# Rover_BeagleBone_Cape.net
KiCad netlist of a schematic drawn in EAGLE
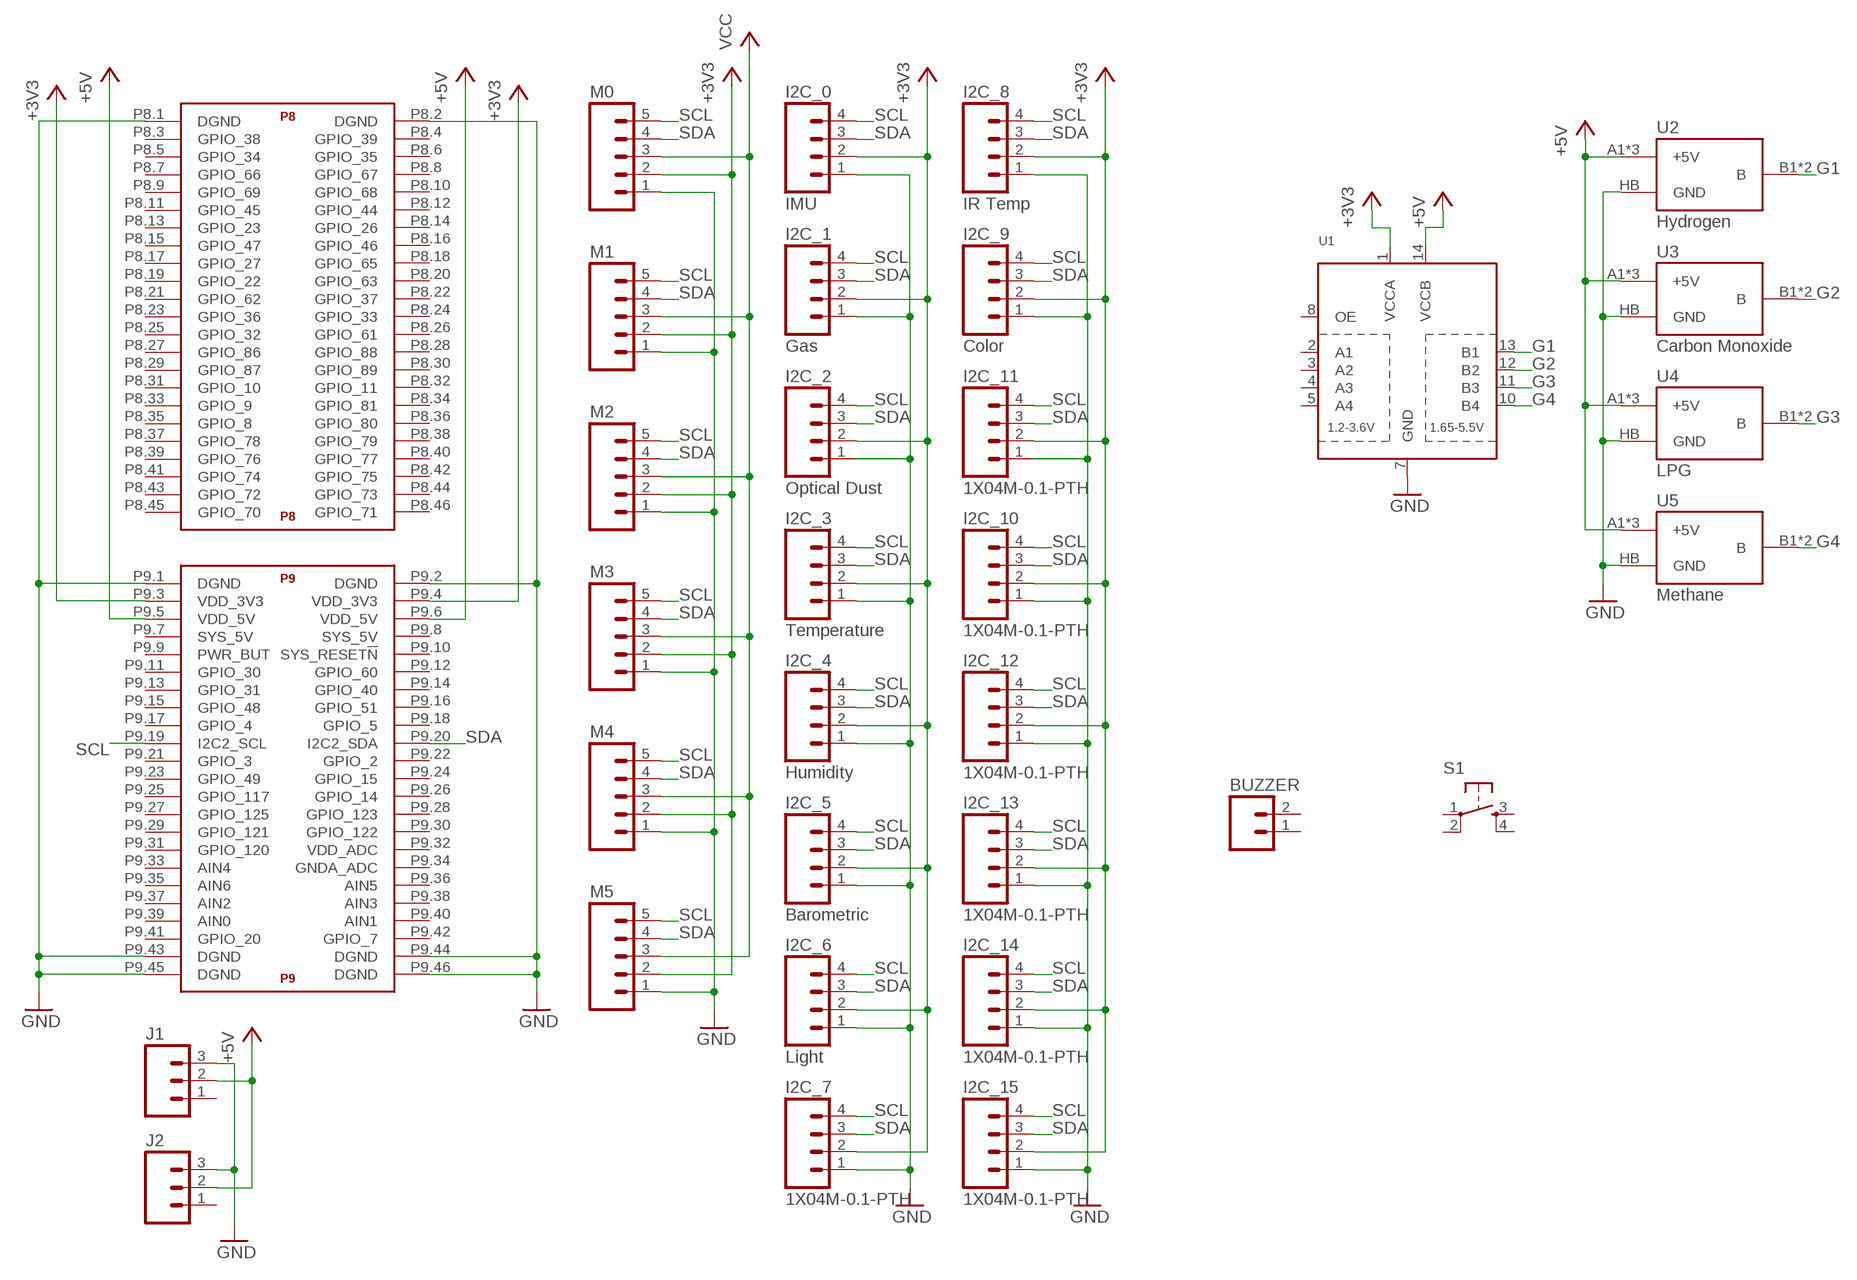
[diagram p0: schematic, sheet 1]

(export (version "E")
  (design (tool "Eeschema 10.0.6"))
  (components
    (comp (ref "BUZZER")
      (value "1X02M-0.1-PTH")
      (footprint "eagle-import:M-1X02-0.1-PTH")
      (libsource (lib "eagle-import") (part "1X02M-0.1-PTH"))
    )
    (comp (ref "I2C_0")
      (value "IMU")
      (footprint "eagle-import:M-1X04-0.1-PTH")
      (libsource (lib "eagle-import") (part "1X04M-0.1-PTH"))
    )
    (comp (ref "I2C_1")
      (value "Gas")
      (footprint "eagle-import:M-1X04-0.1-PTH")
      (libsource (lib "eagle-import") (part "1X04M-0.1-PTH"))
    )
    (comp (ref "I2C_2")
      (value "Optical Dust")
      (footprint "eagle-import:M-1X04-0.1-PTH")
      (libsource (lib "eagle-import") (part "1X04M-0.1-PTH"))
    )
    (comp (ref "I2C_3")
      (value "Temperature")
      (footprint "eagle-import:M-1X04-0.1-PTH")
      (libsource (lib "eagle-import") (part "1X04M-0.1-PTH"))
    )
    (comp (ref "I2C_4")
      (value "Humidity")
      (footprint "eagle-import:M-1X04-0.1-PTH")
      (libsource (lib "eagle-import") (part "1X04M-0.1-PTH"))
    )
    (comp (ref "I2C_5")
      (value "Barometric")
      (footprint "eagle-import:M-1X04-0.1-PTH")
      (libsource (lib "eagle-import") (part "1X04M-0.1-PTH"))
    )
    (comp (ref "I2C_6")
      (value "Light")
      (footprint "eagle-import:M-1X04-0.1-PTH")
      (libsource (lib "eagle-import") (part "1X04M-0.1-PTH"))
    )
    (comp (ref "I2C_7")
      (value "1X04M-0.1-PTH")
      (footprint "eagle-import:M-1X04-0.1-PTH")
      (libsource (lib "eagle-import") (part "1X04M-0.1-PTH"))
    )
    (comp (ref "I2C_8")
      (value "IR Temp")
      (footprint "eagle-import:M-1X04-0.1-PTH")
      (libsource (lib "eagle-import") (part "1X04M-0.1-PTH"))
    )
    (comp (ref "I2C_9")
      (value "Color")
      (footprint "eagle-import:M-1X04-0.1-PTH")
      (libsource (lib "eagle-import") (part "1X04M-0.1-PTH"))
    )
    (comp (ref "I2C_10")
      (value "1X04M-0.1-PTH")
      (footprint "eagle-import:M-1X04-0.1-PTH")
      (libsource (lib "eagle-import") (part "1X04M-0.1-PTH"))
    )
    (comp (ref "I2C_11")
      (value "1X04M-0.1-PTH")
      (footprint "eagle-import:M-1X04-0.1-PTH")
      (libsource (lib "eagle-import") (part "1X04M-0.1-PTH"))
    )
    (comp (ref "I2C_12")
      (value "1X04M-0.1-PTH")
      (footprint "eagle-import:M-1X04-0.1-PTH")
      (libsource (lib "eagle-import") (part "1X04M-0.1-PTH"))
    )
    (comp (ref "I2C_13")
      (value "1X04M-0.1-PTH")
      (footprint "eagle-import:M-1X04-0.1-PTH")
      (libsource (lib "eagle-import") (part "1X04M-0.1-PTH"))
    )
    (comp (ref "I2C_14")
      (value "1X04M-0.1-PTH")
      (footprint "eagle-import:M-1X04-0.1-PTH")
      (libsource (lib "eagle-import") (part "1X04M-0.1-PTH"))
    )
    (comp (ref "I2C_15")
      (value "1X04M-0.1-PTH")
      (footprint "eagle-import:M-1X04-0.1-PTH")
      (libsource (lib "eagle-import") (part "1X04M-0.1-PTH"))
    )
    (comp (ref "J1")
      (value "1X03M-0.1-PTH")
      (footprint "eagle-import:M-1X03-0.1-PTH")
      (libsource (lib "eagle-import") (part "1X03M-0.1-PTH"))
    )
    (comp (ref "J2")
      (value "1X03M-0.1-PTH")
      (footprint "eagle-import:M-1X03-0.1-PTH")
      (libsource (lib "eagle-import") (part "1X03M-0.1-PTH"))
    )
    (comp (ref "M0")
      (value "1X05M-0.1-PTH")
      (footprint "eagle-import:M-1X05-0.1-PTH")
      (libsource (lib "eagle-import") (part "1X05M-0.1-PTH"))
    )
    (comp (ref "M1")
      (value "1X05M-0.1-PTH")
      (footprint "eagle-import:M-1X05-0.1-PTH")
      (libsource (lib "eagle-import") (part "1X05M-0.1-PTH"))
    )
    (comp (ref "M2")
      (value "1X05M-0.1-PTH")
      (footprint "eagle-import:M-1X05-0.1-PTH")
      (libsource (lib "eagle-import") (part "1X05M-0.1-PTH"))
    )
    (comp (ref "M3")
      (value "1X05M-0.1-PTH")
      (footprint "eagle-import:M-1X05-0.1-PTH")
      (libsource (lib "eagle-import") (part "1X05M-0.1-PTH"))
    )
    (comp (ref "M4")
      (value "1X05M-0.1-PTH")
      (footprint "eagle-import:M-1X05-0.1-PTH")
      (libsource (lib "eagle-import") (part "1X05M-0.1-PTH"))
    )
    (comp (ref "M5")
      (value "1X05M-0.1-PTH")
      (footprint "eagle-import:M-1X05-0.1-PTH")
      (libsource (lib "eagle-import") (part "1X05M-0.1-PTH"))
    )
    (comp (ref "S1")
      (value "SWITCH-TACTILESMD")
      (footprint "eagle-import:SWITCH-TACTILE-SMD")
      (libsource (lib "eagle-import") (part "SWITCH-TACTILESMD"))
    )
    (comp (ref "U$1")
      (value "BEAGLE_BONE_BLACK_CAPE")
      (footprint "eagle-import:BEAGLE_BONE_BLACK_CAPE")
      (libsource (lib "eagle-import") (part "BEAGLE_BONE_BLACK_CAPE"))
    )
    (comp (ref "U1")
      (value "TXB0104PWR")
      (footprint "eagle-import:TSSOP14")
      (libsource (lib "eagle-import") (part "TXB0104PWR"))
    )
    (comp (ref "U2")
      (value "Hydrogen")
      (footprint "eagle-import:MQ-X")
      (libsource (lib "eagle-import") (part "GAS-SENSORMQ"))
    )
    (comp (ref "U3")
      (value "Carbon Monoxide")
      (footprint "eagle-import:MQ-X")
      (libsource (lib "eagle-import") (part "GAS-SENSORMQ"))
    )
    (comp (ref "U4")
      (value "LPG")
      (footprint "eagle-import:MQ-X")
      (libsource (lib "eagle-import") (part "GAS-SENSORMQ"))
    )
    (comp (ref "U5")
      (value "Methane")
      (footprint "eagle-import:MQ-X")
      (libsource (lib "eagle-import") (part "GAS-SENSORMQ"))
    )
  )
  (nets
    (net (code "1") (name "+3V3") (class "Default")
      (node (ref "I2C_0") (pin "2") (pinfunction "2_2") (pintype "passive"))
      (node (ref "I2C_1") (pin "2") (pinfunction "2_2") (pintype "passive"))
      (node (ref "I2C_10") (pin "2") (pinfunction "2_2") (pintype "passive"))
      (node (ref "I2C_11") (pin "2") (pinfunction "2_2") (pintype "passive"))
      (node (ref "I2C_12") (pin "2") (pinfunction "2_2") (pintype "passive"))
      (node (ref "I2C_13") (pin "2") (pinfunction "2_2") (pintype "passive"))
      (node (ref "I2C_14") (pin "2") (pinfunction "2_2") (pintype "passive"))
      (node (ref "I2C_15") (pin "2") (pinfunction "2_2") (pintype "passive"))
      (node (ref "I2C_2") (pin "2") (pinfunction "2_2") (pintype "passive"))
      (node (ref "I2C_3") (pin "2") (pinfunction "2_2") (pintype "passive"))
      (node (ref "I2C_4") (pin "2") (pinfunction "2_2") (pintype "passive"))
      (node (ref "I2C_5") (pin "2") (pinfunction "2_2") (pintype "passive"))
      (node (ref "I2C_6") (pin "2") (pinfunction "2_2") (pintype "passive"))
      (node (ref "I2C_7") (pin "2") (pinfunction "2_2") (pintype "passive"))
      (node (ref "I2C_8") (pin "2") (pinfunction "2_2") (pintype "passive"))
      (node (ref "I2C_9") (pin "2") (pinfunction "2_2") (pintype "passive"))
      (node (ref "M0") (pin "2") (pinfunction "2_2") (pintype "passive"))
      (node (ref "M1") (pin "2") (pinfunction "2_2") (pintype "passive"))
      (node (ref "M2") (pin "2") (pinfunction "2_2") (pintype "passive"))
      (node (ref "M3") (pin "2") (pinfunction "2_2") (pintype "passive"))
      (node (ref "M4") (pin "2") (pinfunction "2_2") (pintype "passive"))
      (node (ref "M5") (pin "2") (pinfunction "2_2") (pintype "passive"))
      (node (ref "U$1") (pin "P9.3") (pinfunction "VDD_3V3_P9.3") (pintype "bidirectional"))
      (node (ref "U$1") (pin "P9.4") (pinfunction "VDD_3V3_P9.4") (pintype "bidirectional"))
      (node (ref "U1") (pin "1") (pinfunction "VCCA_1") (pintype "bidirectional"))
    )
    (net (code "2") (name "+5V") (class "Default")
      (node (ref "J1") (pin "2") (pinfunction "2_2") (pintype "passive"))
      (node (ref "J2") (pin "2") (pinfunction "2_2") (pintype "passive"))
      (node (ref "U$1") (pin "P9.5") (pinfunction "VDD_5V_P9.5") (pintype "bidirectional"))
      (node (ref "U$1") (pin "P9.6") (pinfunction "VDD_5V_P9.6") (pintype "bidirectional"))
      (node (ref "U1") (pin "14") (pinfunction "VCCB_14") (pintype "bidirectional"))
      (node (ref "U2") (pin "A1") (pinfunction "+5V_A1") (pintype "power_in"))
      (node (ref "U2") (pin "A2") (pinfunction "+5V_A2") (pintype "power_in"))
      (node (ref "U2") (pin "HA") (pinfunction "+5V_HA") (pintype "power_in"))
      (node (ref "U3") (pin "A1") (pinfunction "+5V_A1") (pintype "power_in"))
      (node (ref "U3") (pin "A2") (pinfunction "+5V_A2") (pintype "power_in"))
      (node (ref "U3") (pin "HA") (pinfunction "+5V_HA") (pintype "power_in"))
      (node (ref "U4") (pin "A1") (pinfunction "+5V_A1") (pintype "power_in"))
      (node (ref "U4") (pin "A2") (pinfunction "+5V_A2") (pintype "power_in"))
      (node (ref "U4") (pin "HA") (pinfunction "+5V_HA") (pintype "power_in"))
      (node (ref "U5") (pin "A1") (pinfunction "+5V_A1") (pintype "power_in"))
      (node (ref "U5") (pin "A2") (pinfunction "+5V_A2") (pintype "power_in"))
      (node (ref "U5") (pin "HA") (pinfunction "+5V_HA") (pintype "power_in"))
    )
    (net (code "3") (name "/G1") (class "Default")
      (node (ref "U1") (pin "13") (pinfunction "B1_13") (pintype "bidirectional"))
      (node (ref "U2") (pin "B1") (pinfunction "B_B1") (pintype "output"))
      (node (ref "U2") (pin "B2") (pinfunction "B_B2") (pintype "output"))
    )
    (net (code "4") (name "/G2") (class "Default")
      (node (ref "U1") (pin "12") (pinfunction "B2_12") (pintype "bidirectional"))
      (node (ref "U3") (pin "B1") (pinfunction "B_B1") (pintype "output"))
      (node (ref "U3") (pin "B2") (pinfunction "B_B2") (pintype "output"))
    )
    (net (code "5") (name "/G3") (class "Default")
      (node (ref "U1") (pin "11") (pinfunction "B3_11") (pintype "bidirectional"))
      (node (ref "U4") (pin "B1") (pinfunction "B_B1") (pintype "output"))
      (node (ref "U4") (pin "B2") (pinfunction "B_B2") (pintype "output"))
    )
    (net (code "6") (name "/G4") (class "Default")
      (node (ref "U1") (pin "10") (pinfunction "B4_10") (pintype "bidirectional"))
      (node (ref "U5") (pin "B1") (pinfunction "B_B1") (pintype "output"))
      (node (ref "U5") (pin "B2") (pinfunction "B_B2") (pintype "output"))
    )
    (net (code "7") (name "/SCL") (class "Default")
      (node (ref "I2C_0") (pin "4") (pinfunction "4_4") (pintype "passive"))
      (node (ref "I2C_1") (pin "4") (pinfunction "4_4") (pintype "passive"))
      (node (ref "I2C_10") (pin "4") (pinfunction "4_4") (pintype "passive"))
      (node (ref "I2C_11") (pin "4") (pinfunction "4_4") (pintype "passive"))
      (node (ref "I2C_12") (pin "4") (pinfunction "4_4") (pintype "passive"))
      (node (ref "I2C_13") (pin "4") (pinfunction "4_4") (pintype "passive"))
      (node (ref "I2C_14") (pin "4") (pinfunction "4_4") (pintype "passive"))
      (node (ref "I2C_15") (pin "4") (pinfunction "4_4") (pintype "passive"))
      (node (ref "I2C_2") (pin "4") (pinfunction "4_4") (pintype "passive"))
      (node (ref "I2C_3") (pin "4") (pinfunction "4_4") (pintype "passive"))
      (node (ref "I2C_4") (pin "4") (pinfunction "4_4") (pintype "passive"))
      (node (ref "I2C_5") (pin "4") (pinfunction "4_4") (pintype "passive"))
      (node (ref "I2C_6") (pin "4") (pinfunction "4_4") (pintype "passive"))
      (node (ref "I2C_7") (pin "4") (pinfunction "4_4") (pintype "passive"))
      (node (ref "I2C_8") (pin "4") (pinfunction "4_4") (pintype "passive"))
      (node (ref "I2C_9") (pin "4") (pinfunction "4_4") (pintype "passive"))
      (node (ref "M0") (pin "5") (pinfunction "5_5") (pintype "passive"))
      (node (ref "M1") (pin "5") (pinfunction "5_5") (pintype "passive"))
      (node (ref "M2") (pin "5") (pinfunction "5_5") (pintype "passive"))
      (node (ref "M3") (pin "5") (pinfunction "5_5") (pintype "passive"))
      (node (ref "M4") (pin "5") (pinfunction "5_5") (pintype "passive"))
      (node (ref "M5") (pin "5") (pinfunction "5_5") (pintype "passive"))
      (node (ref "U$1") (pin "P9.19") (pinfunction "I2C2_SCL_P9.19") (pintype "bidirectional"))
    )
    (net (code "8") (name "/SDA") (class "Default")
      (node (ref "I2C_0") (pin "3") (pinfunction "3_3") (pintype "passive"))
      (node (ref "I2C_1") (pin "3") (pinfunction "3_3") (pintype "passive"))
      (node (ref "I2C_10") (pin "3") (pinfunction "3_3") (pintype "passive"))
      (node (ref "I2C_11") (pin "3") (pinfunction "3_3") (pintype "passive"))
      (node (ref "I2C_12") (pin "3") (pinfunction "3_3") (pintype "passive"))
      (node (ref "I2C_13") (pin "3") (pinfunction "3_3") (pintype "passive"))
      (node (ref "I2C_14") (pin "3") (pinfunction "3_3") (pintype "passive"))
      (node (ref "I2C_15") (pin "3") (pinfunction "3_3") (pintype "passive"))
      (node (ref "I2C_2") (pin "3") (pinfunction "3_3") (pintype "passive"))
      (node (ref "I2C_3") (pin "3") (pinfunction "3_3") (pintype "passive"))
      (node (ref "I2C_4") (pin "3") (pinfunction "3_3") (pintype "passive"))
      (node (ref "I2C_5") (pin "3") (pinfunction "3_3") (pintype "passive"))
      (node (ref "I2C_6") (pin "3") (pinfunction "3_3") (pintype "passive"))
      (node (ref "I2C_7") (pin "3") (pinfunction "3_3") (pintype "passive"))
      (node (ref "I2C_8") (pin "3") (pinfunction "3_3") (pintype "passive"))
      (node (ref "I2C_9") (pin "3") (pinfunction "3_3") (pintype "passive"))
      (node (ref "M0") (pin "4") (pinfunction "4_4") (pintype "passive"))
      (node (ref "M1") (pin "4") (pinfunction "4_4") (pintype "passive"))
      (node (ref "M2") (pin "4") (pinfunction "4_4") (pintype "passive"))
      (node (ref "M3") (pin "4") (pinfunction "4_4") (pintype "passive"))
      (node (ref "M4") (pin "4") (pinfunction "4_4") (pintype "passive"))
      (node (ref "M5") (pin "4") (pinfunction "4_4") (pintype "passive"))
      (node (ref "U$1") (pin "P9.20") (pinfunction "I2C2_SDA_P9.20") (pintype "bidirectional"))
    )
    (net (code "9") (name "GND") (class "Default")
      (node (ref "I2C_0") (pin "1") (pinfunction "1_1") (pintype "passive"))
      (node (ref "I2C_1") (pin "1") (pinfunction "1_1") (pintype "passive"))
      (node (ref "I2C_10") (pin "1") (pinfunction "1_1") (pintype "passive"))
      (node (ref "I2C_11") (pin "1") (pinfunction "1_1") (pintype "passive"))
      (node (ref "I2C_12") (pin "1") (pinfunction "1_1") (pintype "passive"))
      (node (ref "I2C_13") (pin "1") (pinfunction "1_1") (pintype "passive"))
      (node (ref "I2C_14") (pin "1") (pinfunction "1_1") (pintype "passive"))
      (node (ref "I2C_15") (pin "1") (pinfunction "1_1") (pintype "passive"))
      (node (ref "I2C_2") (pin "1") (pinfunction "1_1") (pintype "passive"))
      (node (ref "I2C_3") (pin "1") (pinfunction "1_1") (pintype "passive"))
      (node (ref "I2C_4") (pin "1") (pinfunction "1_1") (pintype "passive"))
      (node (ref "I2C_5") (pin "1") (pinfunction "1_1") (pintype "passive"))
      (node (ref "I2C_6") (pin "1") (pinfunction "1_1") (pintype "passive"))
      (node (ref "I2C_7") (pin "1") (pinfunction "1_1") (pintype "passive"))
      (node (ref "I2C_8") (pin "1") (pinfunction "1_1") (pintype "passive"))
      (node (ref "I2C_9") (pin "1") (pinfunction "1_1") (pintype "passive"))
      (node (ref "J1") (pin "3") (pinfunction "3_3") (pintype "passive"))
      (node (ref "J2") (pin "3") (pinfunction "3_3") (pintype "passive"))
      (node (ref "M0") (pin "1") (pinfunction "1_1") (pintype "passive"))
      (node (ref "M1") (pin "1") (pinfunction "1_1") (pintype "passive"))
      (node (ref "M2") (pin "1") (pinfunction "1_1") (pintype "passive"))
      (node (ref "M3") (pin "1") (pinfunction "1_1") (pintype "passive"))
      (node (ref "M4") (pin "1") (pinfunction "1_1") (pintype "passive"))
      (node (ref "M5") (pin "1") (pinfunction "1_1") (pintype "passive"))
      (node (ref "U$1") (pin "P8.1") (pinfunction "DGND_P8.1") (pintype "bidirectional"))
      (node (ref "U$1") (pin "P8.2") (pinfunction "DGND_P8.2") (pintype "bidirectional"))
      (node (ref "U$1") (pin "P9.1") (pinfunction "DGND_P9.1") (pintype "bidirectional"))
      (node (ref "U$1") (pin "P9.2") (pinfunction "DGND_P9.2") (pintype "bidirectional"))
      (node (ref "U$1") (pin "P9.43") (pinfunction "DGND_P9.43") (pintype "bidirectional"))
      (node (ref "U$1") (pin "P9.44") (pinfunction "DGND_P9.44") (pintype "bidirectional"))
      (node (ref "U$1") (pin "P9.45") (pinfunction "DGND_P9.45") (pintype "bidirectional"))
      (node (ref "U$1") (pin "P9.46") (pinfunction "DGND_P9.46") (pintype "bidirectional"))
      (node (ref "U1") (pin "7") (pinfunction "GND_7") (pintype "bidirectional"))
      (node (ref "U2") (pin "HB") (pinfunction "GND_HB") (pintype "power_in"))
      (node (ref "U3") (pin "HB") (pinfunction "GND_HB") (pintype "power_in"))
      (node (ref "U4") (pin "HB") (pinfunction "GND_HB") (pintype "power_in"))
      (node (ref "U5") (pin "HB") (pinfunction "GND_HB") (pintype "power_in"))
    )
    (net (code "10") (name "VCC") (class "Default")
      (node (ref "M0") (pin "3") (pinfunction "3_3") (pintype "passive"))
      (node (ref "M1") (pin "3") (pinfunction "3_3") (pintype "passive"))
      (node (ref "M2") (pin "3") (pinfunction "3_3") (pintype "passive"))
      (node (ref "M3") (pin "3") (pinfunction "3_3") (pintype "passive"))
      (node (ref "M4") (pin "3") (pinfunction "3_3") (pintype "passive"))
      (node (ref "M5") (pin "3") (pinfunction "3_3") (pintype "passive"))
    )
    (net (code "11") (name "unconnected-(BUZZER-Pad1)") (class "Default")
      (node (ref "BUZZER") (pin "1") (pinfunction "1_1") (pintype "passive"))
    )
    (net (code "12") (name "unconnected-(BUZZER-Pad2)") (class "Default")
      (node (ref "BUZZER") (pin "2") (pinfunction "2_2") (pintype "passive"))
    )
    (net (code "13") (name "unconnected-(J1-Pad1)") (class "Default")
      (node (ref "J1") (pin "1") (pinfunction "1_1") (pintype "passive"))
    )
    (net (code "14") (name "unconnected-(J2-Pad1)") (class "Default")
      (node (ref "J2") (pin "1") (pinfunction "1_1") (pintype "passive"))
    )
    (net (code "15") (name "unconnected-(S1-Pad1)") (class "Default")
      (node (ref "S1") (pin "1") (pinfunction "1_1") (pintype "passive"))
    )
    (net (code "16") (name "unconnected-(S1-Pad2)") (class "Default")
      (node (ref "S1") (pin "2") (pinfunction "2_2") (pintype "passive"))
    )
    (net (code "17") (name "unconnected-(S1-Pad3)") (class "Default")
      (node (ref "S1") (pin "3") (pinfunction "3_3") (pintype "passive"))
    )
    (net (code "18") (name "unconnected-(S1-Pad4)") (class "Default")
      (node (ref "S1") (pin "4") (pinfunction "4_4") (pintype "passive"))
    )
    (net (code "19") (name "unconnected-(U$1A-GPIO_8-PadP8.35)") (class "Default")
      (node (ref "U$1") (pin "P8.35") (pinfunction "GPIO_8_P8.35") (pintype "bidirectional"))
    )
    (net (code "20") (name "unconnected-(U$1A-GPIO_9-PadP8.33)") (class "Default")
      (node (ref "U$1") (pin "P8.33") (pinfunction "GPIO_9_P8.33") (pintype "bidirectional"))
    )
    (net (code "21") (name "unconnected-(U$1A-GPIO_10-PadP8.31)") (class "Default")
      (node (ref "U$1") (pin "P8.31") (pinfunction "GPIO_10_P8.31") (pintype "bidirectional"))
    )
    (net (code "22") (name "unconnected-(U$1A-GPIO_11-PadP8.32)") (class "Default")
      (node (ref "U$1") (pin "P8.32") (pinfunction "GPIO_11_P8.32") (pintype "bidirectional"))
    )
    (net (code "23") (name "unconnected-(U$1A-GPIO_22-PadP8.19)") (class "Default")
      (node (ref "U$1") (pin "P8.19") (pinfunction "GPIO_22_P8.19") (pintype "bidirectional"))
    )
    (net (code "24") (name "unconnected-(U$1A-GPIO_23-PadP8.13)") (class "Default")
      (node (ref "U$1") (pin "P8.13") (pinfunction "GPIO_23_P8.13") (pintype "bidirectional"))
    )
    (net (code "25") (name "unconnected-(U$1A-GPIO_26-PadP8.14)") (class "Default")
      (node (ref "U$1") (pin "P8.14") (pinfunction "GPIO_26_P8.14") (pintype "bidirectional"))
    )
    (net (code "26") (name "unconnected-(U$1A-GPIO_27-PadP8.17)") (class "Default")
      (node (ref "U$1") (pin "P8.17") (pinfunction "GPIO_27_P8.17") (pintype "bidirectional"))
    )
    (net (code "27") (name "unconnected-(U$1A-GPIO_32-PadP8.25)") (class "Default")
      (node (ref "U$1") (pin "P8.25") (pinfunction "GPIO_32_P8.25") (pintype "bidirectional"))
    )
    (net (code "28") (name "unconnected-(U$1A-GPIO_33-PadP8.24)") (class "Default")
      (node (ref "U$1") (pin "P8.24") (pinfunction "GPIO_33_P8.24") (pintype "bidirectional"))
    )
    (net (code "29") (name "unconnected-(U$1A-GPIO_34-PadP8.5)") (class "Default")
      (node (ref "U$1") (pin "P8.5") (pinfunction "GPIO_34_P8.5") (pintype "bidirectional"))
    )
    (net (code "30") (name "unconnected-(U$1A-GPIO_35-PadP8.6)") (class "Default")
      (node (ref "U$1") (pin "P8.6") (pinfunction "GPIO_35_P8.6") (pintype "bidirectional"))
    )
    (net (code "31") (name "unconnected-(U$1A-GPIO_36-PadP8.23)") (class "Default")
      (node (ref "U$1") (pin "P8.23") (pinfunction "GPIO_36_P8.23") (pintype "bidirectional"))
    )
    (net (code "32") (name "unconnected-(U$1A-GPIO_37-PadP8.22)") (class "Default")
      (node (ref "U$1") (pin "P8.22") (pinfunction "GPIO_37_P8.22") (pintype "bidirectional"))
    )
    (net (code "33") (name "unconnected-(U$1A-GPIO_38-PadP8.3)") (class "Default")
      (node (ref "U$1") (pin "P8.3") (pinfunction "GPIO_38_P8.3") (pintype "bidirectional"))
    )
    (net (code "34") (name "unconnected-(U$1A-GPIO_39-PadP8.4)") (class "Default")
      (node (ref "U$1") (pin "P8.4") (pinfunction "GPIO_39_P8.4") (pintype "bidirectional"))
    )
    (net (code "35") (name "unconnected-(U$1A-GPIO_44-PadP8.12)") (class "Default")
      (node (ref "U$1") (pin "P8.12") (pinfunction "GPIO_44_P8.12") (pintype "bidirectional"))
    )
    (net (code "36") (name "unconnected-(U$1A-GPIO_45-PadP8.11)") (class "Default")
      (node (ref "U$1") (pin "P8.11") (pinfunction "GPIO_45_P8.11") (pintype "bidirectional"))
    )
    (net (code "37") (name "unconnected-(U$1A-GPIO_46-PadP8.16)") (class "Default")
      (node (ref "U$1") (pin "P8.16") (pinfunction "GPIO_46_P8.16") (pintype "bidirectional"))
    )
    (net (code "38") (name "unconnected-(U$1A-GPIO_47-PadP8.15)") (class "Default")
      (node (ref "U$1") (pin "P8.15") (pinfunction "GPIO_47_P8.15") (pintype "bidirectional"))
    )
    (net (code "39") (name "unconnected-(U$1A-GPIO_61-PadP8.26)") (class "Default")
      (node (ref "U$1") (pin "P8.26") (pinfunction "GPIO_61_P8.26") (pintype "bidirectional"))
    )
    (net (code "40") (name "unconnected-(U$1A-GPIO_62-PadP8.21)") (class "Default")
      (node (ref "U$1") (pin "P8.21") (pinfunction "GPIO_62_P8.21") (pintype "bidirectional"))
    )
    (net (code "41") (name "unconnected-(U$1A-GPIO_63-PadP8.20)") (class "Default")
      (node (ref "U$1") (pin "P8.20") (pinfunction "GPIO_63_P8.20") (pintype "bidirectional"))
    )
    (net (code "42") (name "unconnected-(U$1A-GPIO_65-PadP8.18)") (class "Default")
      (node (ref "U$1") (pin "P8.18") (pinfunction "GPIO_65_P8.18") (pintype "bidirectional"))
    )
    (net (code "43") (name "unconnected-(U$1A-GPIO_66-PadP8.7)") (class "Default")
      (node (ref "U$1") (pin "P8.7") (pinfunction "GPIO_66_P8.7") (pintype "bidirectional"))
    )
    (net (code "44") (name "unconnected-(U$1A-GPIO_67-PadP8.8)") (class "Default")
      (node (ref "U$1") (pin "P8.8") (pinfunction "GPIO_67_P8.8") (pintype "bidirectional"))
    )
    (net (code "45") (name "unconnected-(U$1A-GPIO_68-PadP8.10)") (class "Default")
      (node (ref "U$1") (pin "P8.10") (pinfunction "GPIO_68_P8.10") (pintype "bidirectional"))
    )
    (net (code "46") (name "unconnected-(U$1A-GPIO_69-PadP8.9)") (class "Default")
      (node (ref "U$1") (pin "P8.9") (pinfunction "GPIO_69_P8.9") (pintype "bidirectional"))
    )
    (net (code "47") (name "unconnected-(U$1A-GPIO_70-PadP8.45)") (class "Default")
      (node (ref "U$1") (pin "P8.45") (pinfunction "GPIO_70_P8.45") (pintype "bidirectional"))
    )
    (net (code "48") (name "unconnected-(U$1A-GPIO_71-PadP8.46)") (class "Default")
      (node (ref "U$1") (pin "P8.46") (pinfunction "GPIO_71_P8.46") (pintype "bidirectional"))
    )
    (net (code "49") (name "unconnected-(U$1A-GPIO_72-PadP8.43)") (class "Default")
      (node (ref "U$1") (pin "P8.43") (pinfunction "GPIO_72_P8.43") (pintype "bidirectional"))
    )
    (net (code "50") (name "unconnected-(U$1A-GPIO_73-PadP8.44)") (class "Default")
      (node (ref "U$1") (pin "P8.44") (pinfunction "GPIO_73_P8.44") (pintype "bidirectional"))
    )
    (net (code "51") (name "unconnected-(U$1A-GPIO_74-PadP8.41)") (class "Default")
      (node (ref "U$1") (pin "P8.41") (pinfunction "GPIO_74_P8.41") (pintype "bidirectional"))
    )
    (net (code "52") (name "unconnected-(U$1A-GPIO_75-PadP8.42)") (class "Default")
      (node (ref "U$1") (pin "P8.42") (pinfunction "GPIO_75_P8.42") (pintype "bidirectional"))
    )
    (net (code "53") (name "unconnected-(U$1A-GPIO_76-PadP8.39)") (class "Default")
      (node (ref "U$1") (pin "P8.39") (pinfunction "GPIO_76_P8.39") (pintype "bidirectional"))
    )
    (net (code "54") (name "unconnected-(U$1A-GPIO_77-PadP8.40)") (class "Default")
      (node (ref "U$1") (pin "P8.40") (pinfunction "GPIO_77_P8.40") (pintype "bidirectional"))
    )
    (net (code "55") (name "unconnected-(U$1A-GPIO_78-PadP8.37)") (class "Default")
      (node (ref "U$1") (pin "P8.37") (pinfunction "GPIO_78_P8.37") (pintype "bidirectional"))
    )
    (net (code "56") (name "unconnected-(U$1A-GPIO_79-PadP8.38)") (class "Default")
      (node (ref "U$1") (pin "P8.38") (pinfunction "GPIO_79_P8.38") (pintype "bidirectional"))
    )
    (net (code "57") (name "unconnected-(U$1A-GPIO_80-PadP8.36)") (class "Default")
      (node (ref "U$1") (pin "P8.36") (pinfunction "GPIO_80_P8.36") (pintype "bidirectional"))
    )
    (net (code "58") (name "unconnected-(U$1A-GPIO_81-PadP8.34)") (class "Default")
      (node (ref "U$1") (pin "P8.34") (pinfunction "GPIO_81_P8.34") (pintype "bidirectional"))
    )
    (net (code "59") (name "unconnected-(U$1A-GPIO_86-PadP8.27)") (class "Default")
      (node (ref "U$1") (pin "P8.27") (pinfunction "GPIO_86_P8.27") (pintype "bidirectional"))
    )
    (net (code "60") (name "unconnected-(U$1A-GPIO_87-PadP8.29)") (class "Default")
      (node (ref "U$1") (pin "P8.29") (pinfunction "GPIO_87_P8.29") (pintype "bidirectional"))
    )
    (net (code "61") (name "unconnected-(U$1A-GPIO_88-PadP8.28)") (class "Default")
      (node (ref "U$1") (pin "P8.28") (pinfunction "GPIO_88_P8.28") (pintype "bidirectional"))
    )
    (net (code "62") (name "unconnected-(U$1A-GPIO_89-PadP8.30)") (class "Default")
      (node (ref "U$1") (pin "P8.30") (pinfunction "GPIO_89_P8.30") (pintype "bidirectional"))
    )
    (net (code "63") (name "unconnected-(U$1B-AIN0-PadP9.39)") (class "Default")
      (node (ref "U$1") (pin "P9.39") (pinfunction "AIN0_P9.39") (pintype "bidirectional"))
    )
    (net (code "64") (name "unconnected-(U$1B-AIN1-PadP9.40)") (class "Default")
      (node (ref "U$1") (pin "P9.40") (pinfunction "AIN1_P9.40") (pintype "bidirectional"))
    )
    (net (code "65") (name "unconnected-(U$1B-AIN2-PadP9.37)") (class "Default")
      (node (ref "U$1") (pin "P9.37") (pinfunction "AIN2_P9.37") (pintype "bidirectional"))
    )
    (net (code "66") (name "unconnected-(U$1B-AIN3-PadP9.38)") (class "Default")
      (node (ref "U$1") (pin "P9.38") (pinfunction "AIN3_P9.38") (pintype "bidirectional"))
    )
    (net (code "67") (name "unconnected-(U$1B-AIN4-PadP9.33)") (class "Default")
      (node (ref "U$1") (pin "P9.33") (pinfunction "AIN4_P9.33") (pintype "bidirectional"))
    )
    (net (code "68") (name "unconnected-(U$1B-AIN5-PadP9.36)") (class "Default")
      (node (ref "U$1") (pin "P9.36") (pinfunction "AIN5_P9.36") (pintype "bidirectional"))
    )
    (net (code "69") (name "unconnected-(U$1B-AIN6-PadP9.35)") (class "Default")
      (node (ref "U$1") (pin "P9.35") (pinfunction "AIN6_P9.35") (pintype "bidirectional"))
    )
    (net (code "70") (name "unconnected-(U$1B-GNDA_ADC-PadP9.34)") (class "Default")
      (node (ref "U$1") (pin "P9.34") (pinfunction "GNDA_ADC_P9.34") (pintype "bidirectional"))
    )
    (net (code "71") (name "unconnected-(U$1B-GPIO_2-PadP9.22)") (class "Default")
      (node (ref "U$1") (pin "P9.22") (pinfunction "GPIO_2_P9.22") (pintype "bidirectional"))
    )
    (net (code "72") (name "unconnected-(U$1B-GPIO_3-PadP9.21)") (class "Default")
      (node (ref "U$1") (pin "P9.21") (pinfunction "GPIO_3_P9.21") (pintype "bidirectional"))
    )
    (net (code "73") (name "unconnected-(U$1B-GPIO_4-PadP9.17)") (class "Default")
      (node (ref "U$1") (pin "P9.17") (pinfunction "GPIO_4_P9.17") (pintype "bidirectional"))
    )
    (net (code "74") (name "unconnected-(U$1B-GPIO_5-PadP9.18)") (class "Default")
      (node (ref "U$1") (pin "P9.18") (pinfunction "GPIO_5_P9.18") (pintype "bidirectional"))
    )
    (net (code "75") (name "unconnected-(U$1B-GPIO_7-PadP9.42)") (class "Default")
      (node (ref "U$1") (pin "P9.42") (pinfunction "GPIO_7_P9.42") (pintype "bidirectional"))
    )
    (net (code "76") (name "unconnected-(U$1B-GPIO_14-PadP9.26)") (class "Default")
      (node (ref "U$1") (pin "P9.26") (pinfunction "GPIO_14_P9.26") (pintype "bidirectional"))
    )
    (net (code "77") (name "unconnected-(U$1B-GPIO_15-PadP9.24)") (class "Default")
      (node (ref "U$1") (pin "P9.24") (pinfunction "GPIO_15_P9.24") (pintype "bidirectional"))
    )
    (net (code "78") (name "unconnected-(U$1B-GPIO_20-PadP9.41)") (class "Default")
      (node (ref "U$1") (pin "P9.41") (pinfunction "GPIO_20_P9.41") (pintype "bidirectional"))
    )
    (net (code "79") (name "unconnected-(U$1B-GPIO_30-PadP9.11)") (class "Default")
      (node (ref "U$1") (pin "P9.11") (pinfunction "GPIO_30_P9.11") (pintype "bidirectional"))
    )
    (net (code "80") (name "unconnected-(U$1B-GPIO_31-PadP9.13)") (class "Default")
      (node (ref "U$1") (pin "P9.13") (pinfunction "GPIO_31_P9.13") (pintype "bidirectional"))
    )
    (net (code "81") (name "unconnected-(U$1B-GPIO_40-PadP9.14)") (class "Default")
      (node (ref "U$1") (pin "P9.14") (pinfunction "GPIO_40_P9.14") (pintype "bidirectional"))
    )
    (net (code "82") (name "unconnected-(U$1B-GPIO_48-PadP9.15)") (class "Default")
      (node (ref "U$1") (pin "P9.15") (pinfunction "GPIO_48_P9.15") (pintype "bidirectional"))
    )
    (net (code "83") (name "unconnected-(U$1B-GPIO_49-PadP9.23)") (class "Default")
      (node (ref "U$1") (pin "P9.23") (pinfunction "GPIO_49_P9.23") (pintype "bidirectional"))
    )
    (net (code "84") (name "unconnected-(U$1B-GPIO_51-PadP9.16)") (class "Default")
      (node (ref "U$1") (pin "P9.16") (pinfunction "GPIO_51_P9.16") (pintype "bidirectional"))
    )
    (net (code "85") (name "unconnected-(U$1B-GPIO_60-PadP9.12)") (class "Default")
      (node (ref "U$1") (pin "P9.12") (pinfunction "GPIO_60_P9.12") (pintype "bidirectional"))
    )
    (net (code "86") (name "unconnected-(U$1B-GPIO_117-PadP9.25)") (class "Default")
      (node (ref "U$1") (pin "P9.25") (pinfunction "GPIO_117_P9.25") (pintype "bidirectional"))
    )
    (net (code "87") (name "unconnected-(U$1B-GPIO_120-PadP9.31)") (class "Default")
      (node (ref "U$1") (pin "P9.31") (pinfunction "GPIO_120_P9.31") (pintype "bidirectional"))
    )
    (net (code "88") (name "unconnected-(U$1B-GPIO_121-PadP9.29)") (class "Default")
      (node (ref "U$1") (pin "P9.29") (pinfunction "GPIO_121_P9.29") (pintype "bidirectional"))
    )
    (net (code "89") (name "unconnected-(U$1B-GPIO_122-PadP9.30)") (class "Default")
      (node (ref "U$1") (pin "P9.30") (pinfunction "GPIO_122_P9.30") (pintype "bidirectional"))
    )
    (net (code "90") (name "unconnected-(U$1B-GPIO_123-PadP9.28)") (class "Default")
      (node (ref "U$1") (pin "P9.28") (pinfunction "GPIO_123_P9.28") (pintype "bidirectional"))
    )
    (net (code "91") (name "unconnected-(U$1B-GPIO_125-PadP9.27)") (class "Default")
      (node (ref "U$1") (pin "P9.27") (pinfunction "GPIO_125_P9.27") (pintype "bidirectional"))
    )
    (net (code "92") (name "unconnected-(U$1B-PWR_BUT-PadP9.9)") (class "Default")
      (node (ref "U$1") (pin "P9.9") (pinfunction "PWR_BUT_P9.9") (pintype "bidirectional"))
    )
    (net (code "93") (name "unconnected-(U$1B-SYS_5V-PadP9.7)") (class "Default")
      (node (ref "U$1") (pin "P9.7") (pinfunction "SYS_5V_P9.7") (pintype "bidirectional"))
    )
    (net (code "94") (name "unconnected-(U$1B-SYS_5V-PadP9.8)") (class "Default")
      (node (ref "U$1") (pin "P9.8") (pinfunction "SYS_5V_P9.8") (pintype "bidirectional"))
    )
    (net (code "95") (name "unconnected-(U$1B-SYS_RESET~{N}-PadP9.10)") (class "Default")
      (node (ref "U$1") (pin "P9.10") (pinfunction "SYS_RESET~{N}_P9.10") (pintype "bidirectional"))
    )
    (net (code "96") (name "unconnected-(U$1B-VDD_ADC-PadP9.32)") (class "Default")
      (node (ref "U$1") (pin "P9.32") (pinfunction "VDD_ADC_P9.32") (pintype "bidirectional"))
    )
    (net (code "97") (name "unconnected-(U1-A1-Pad2)") (class "Default")
      (node (ref "U1") (pin "2") (pinfunction "A1_2") (pintype "bidirectional"))
    )
    (net (code "98") (name "unconnected-(U1-A2-Pad3)") (class "Default")
      (node (ref "U1") (pin "3") (pinfunction "A2_3") (pintype "bidirectional"))
    )
    (net (code "99") (name "unconnected-(U1-A3-Pad4)") (class "Default")
      (node (ref "U1") (pin "4") (pinfunction "A3_4") (pintype "bidirectional"))
    )
    (net (code "100") (name "unconnected-(U1-A4-Pad5)") (class "Default")
      (node (ref "U1") (pin "5") (pinfunction "A4_5") (pintype "bidirectional"))
    )
    (net (code "101") (name "unconnected-(U1-OE-Pad8)") (class "Default")
      (node (ref "U1") (pin "8") (pinfunction "OE_8") (pintype "bidirectional"))
    )
  )
)
